# Chronograph.net
KiCad netlist of a schematic drawn in EAGLE
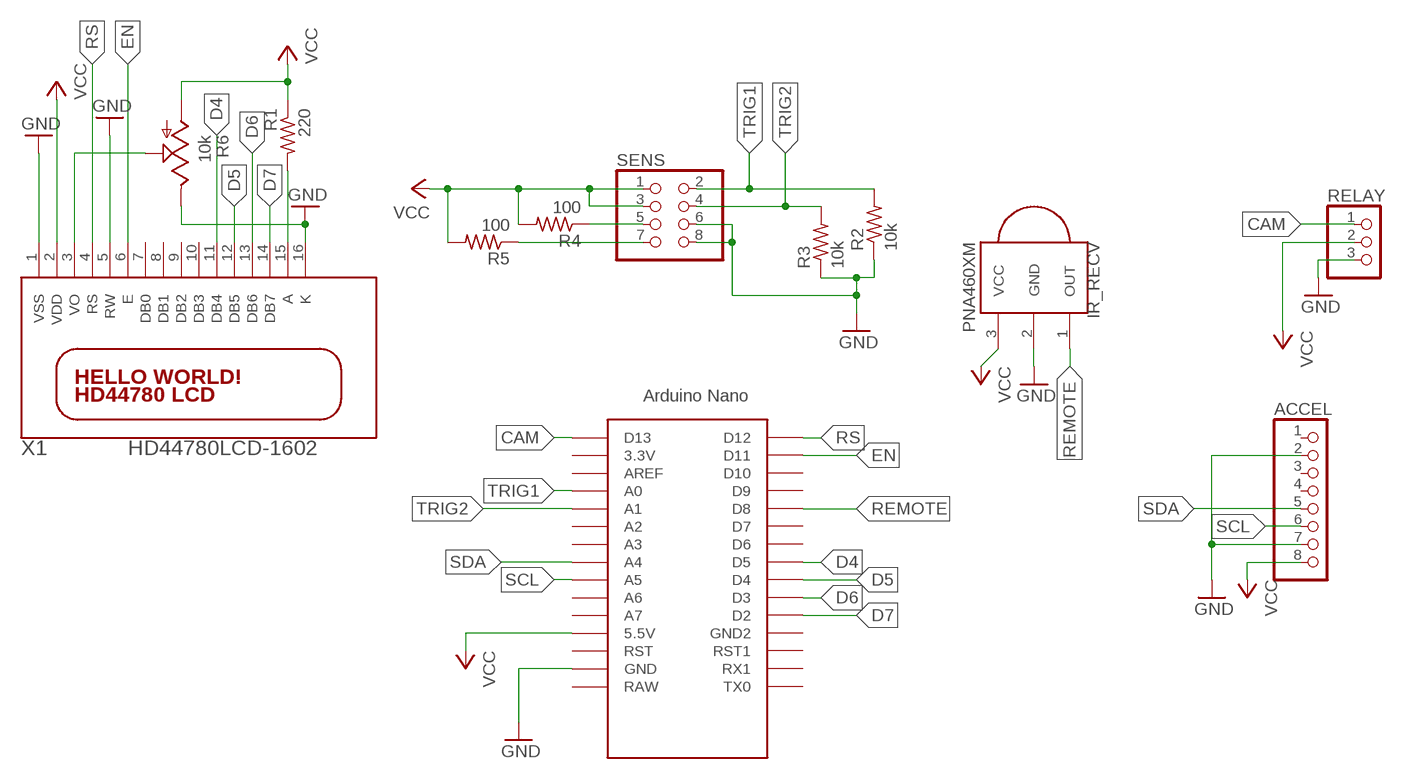
[diagram p0: schematic, sheet 1]

(export (version "E")
  (design (tool "Eeschema 10.0.6"))
  (components
    (comp (ref "ACCEL")
      (value "PINHD-1X8BIG")
      (footprint "eagle-import:1X08-BIG")
      (libsource (lib "eagle-import") (part "PINHD-1X8BIG"))
    )
    (comp (ref "IR_RECV")
      (value "PNA460XM")
      (footprint "eagle-import:PNA460XM")
      (libsource (lib "eagle-import") (part "PNA460XM"))
    )
    (comp (ref "R1")
      (value "220")
      (footprint "eagle-import:0204_7")
      (libsource (lib "eagle-import") (part "R-US_0204/7"))
    )
    (comp (ref "R2")
      (value "10k")
      (footprint "eagle-import:0204_7")
      (libsource (lib "eagle-import") (part "R-US_0204/7"))
    )
    (comp (ref "R3")
      (value "10k")
      (footprint "eagle-import:0204_7")
      (libsource (lib "eagle-import") (part "R-US_0204/7"))
    )
    (comp (ref "R4")
      (value "100")
      (footprint "eagle-import:0204_7")
      (libsource (lib "eagle-import") (part "R-US_0204/7"))
    )
    (comp (ref "R5")
      (value "100")
      (footprint "eagle-import:0204_7")
      (libsource (lib "eagle-import") (part "R-US_0204/7"))
    )
    (comp (ref "R6")
      (value "10k")
      (footprint "eagle-import:B64Y")
      (libsource (lib "eagle-import") (part "TRIM_US-B64Y"))
    )
    (comp (ref "RELAY")
      (value "PINHD-1X3")
      (footprint "eagle-import:1X03")
      (libsource (lib "eagle-import") (part "PINHD-1X3"))
    )
    (comp (ref "SENS")
      (value "PINHD-2X4")
      (footprint "eagle-import:2X04")
      (libsource (lib "eagle-import") (part "PINHD-2X4"))
    )
    (comp (ref "U$1")
      (value "NANO")
      (footprint "eagle-import:NANO")
      (libsource (lib "eagle-import") (part "NANO"))
    )
    (comp (ref "X1")
      (value "HD44780LCD-1602")
      (footprint "eagle-import:LCD1602")
      (libsource (lib "eagle-import") (part "HD44780LCD-1602"))
    )
  )
  (nets
    (net (code "1") (name "CAM") (class "Default")
      (node (ref "RELAY") (pin "1") (pinfunction "1_1") (pintype "passive"))
      (node (ref "U$1") (pin "D13") (pinfunction "D13_D13") (pintype "bidirectional"))
    )
    (net (code "2") (name "D4") (class "Default")
      (node (ref "U$1") (pin "D5") (pinfunction "D5_D5") (pintype "bidirectional"))
      (node (ref "X1") (pin "11") (pinfunction "DB4_11") (pintype "bidirectional"))
    )
    (net (code "3") (name "D5") (class "Default")
      (node (ref "U$1") (pin "D4") (pinfunction "D4_D4") (pintype "bidirectional"))
      (node (ref "X1") (pin "12") (pinfunction "DB5_12") (pintype "bidirectional"))
    )
    (net (code "4") (name "D6") (class "Default")
      (node (ref "U$1") (pin "D3") (pinfunction "D3_D3") (pintype "bidirectional"))
      (node (ref "X1") (pin "13") (pinfunction "DB6_13") (pintype "bidirectional"))
    )
    (net (code "5") (name "D7") (class "Default")
      (node (ref "U$1") (pin "D2") (pinfunction "D2_D2") (pintype "bidirectional"))
      (node (ref "X1") (pin "14") (pinfunction "DB7_14") (pintype "bidirectional"))
    )
    (net (code "6") (name "EN") (class "Default")
      (node (ref "U$1") (pin "D11") (pinfunction "D11_D11") (pintype "bidirectional"))
      (node (ref "X1") (pin "6") (pinfunction "E_6") (pintype "input"))
    )
    (net (code "7") (name "GND") (class "Default")
      (node (ref "ACCEL") (pin "2") (pinfunction "2_2") (pintype "passive"))
      (node (ref "ACCEL") (pin "7") (pinfunction "7_7") (pintype "passive"))
      (node (ref "IR_RECV") (pin "2") (pinfunction "GND_2") (pintype "power_in"))
      (node (ref "R2") (pin "1") (pinfunction "1_1") (pintype "passive"))
      (node (ref "R3") (pin "1") (pinfunction "1_1") (pintype "passive"))
      (node (ref "R6") (pin "E") (pinfunction "E_E") (pintype "passive"))
      (node (ref "RELAY") (pin "3") (pinfunction "3_3") (pintype "passive"))
      (node (ref "SENS") (pin "6") (pinfunction "6_6") (pintype "passive"))
      (node (ref "SENS") (pin "8") (pinfunction "8_8") (pintype "passive"))
      (node (ref "U$1") (pin "GND") (pinfunction "GND_GND") (pintype "bidirectional"))
      (node (ref "X1") (pin "1") (pinfunction "VSS_1") (pintype "power_in"))
      (node (ref "X1") (pin "16") (pinfunction "K_16") (pintype "input"))
      (node (ref "X1") (pin "5") (pinfunction "RW_5") (pintype "input"))
    )
    (net (code "8") (name "Net-(R4-Pad1)") (class "Default")
      (node (ref "R4") (pin "1") (pinfunction "1_1") (pintype "passive"))
      (node (ref "SENS") (pin "5") (pinfunction "5_5") (pintype "passive"))
    )
    (net (code "9") (name "Net-(R5-Pad1)") (class "Default")
      (node (ref "R5") (pin "1") (pinfunction "1_1") (pintype "passive"))
      (node (ref "SENS") (pin "7") (pinfunction "7_7") (pintype "passive"))
    )
    (net (code "10") (name "Net-(X1-A)") (class "Default")
      (node (ref "R1") (pin "2") (pinfunction "2_2") (pintype "passive"))
      (node (ref "X1") (pin "15") (pinfunction "A_15") (pintype "input"))
    )
    (net (code "11") (name "Net-(X1-VO)") (class "Default")
      (node (ref "R6") (pin "S") (pinfunction "S_S") (pintype "passive"))
      (node (ref "X1") (pin "3") (pinfunction "VO_3") (pintype "input"))
    )
    (net (code "12") (name "REMOTE") (class "Default")
      (node (ref "IR_RECV") (pin "1") (pinfunction "OUT_1") (pintype "output"))
      (node (ref "U$1") (pin "D8") (pinfunction "D8_D8") (pintype "bidirectional"))
    )
    (net (code "13") (name "RS") (class "Default")
      (node (ref "U$1") (pin "D12") (pinfunction "D12_D12") (pintype "bidirectional"))
      (node (ref "X1") (pin "4") (pinfunction "RS_4") (pintype "input"))
    )
    (net (code "14") (name "SCL") (class "Default")
      (node (ref "ACCEL") (pin "6") (pinfunction "6_6") (pintype "passive"))
      (node (ref "U$1") (pin "A5") (pinfunction "A5_A5") (pintype "bidirectional"))
    )
    (net (code "15") (name "SDA") (class "Default")
      (node (ref "ACCEL") (pin "5") (pinfunction "5_5") (pintype "passive"))
      (node (ref "U$1") (pin "A4") (pinfunction "A4_A4") (pintype "bidirectional"))
    )
    (net (code "16") (name "TRIG1") (class "Default")
      (node (ref "R2") (pin "2") (pinfunction "2_2") (pintype "passive"))
      (node (ref "SENS") (pin "2") (pinfunction "2_2") (pintype "passive"))
      (node (ref "U$1") (pin "A0") (pinfunction "A0_A0") (pintype "bidirectional"))
    )
    (net (code "17") (name "TRIG2") (class "Default")
      (node (ref "R3") (pin "2") (pinfunction "2_2") (pintype "passive"))
      (node (ref "SENS") (pin "4") (pinfunction "4_4") (pintype "passive"))
      (node (ref "U$1") (pin "A1") (pinfunction "A1_A1") (pintype "bidirectional"))
    )
    (net (code "18") (name "VCC") (class "Default")
      (node (ref "ACCEL") (pin "8") (pinfunction "8_8") (pintype "passive"))
      (node (ref "IR_RECV") (pin "3") (pinfunction "VCC_3") (pintype "power_in"))
      (node (ref "R1") (pin "1") (pinfunction "1_1") (pintype "passive"))
      (node (ref "R4") (pin "2") (pinfunction "2_2") (pintype "passive"))
      (node (ref "R5") (pin "2") (pinfunction "2_2") (pintype "passive"))
      (node (ref "R6") (pin "A") (pinfunction "A_A") (pintype "passive"))
      (node (ref "RELAY") (pin "2") (pinfunction "2_2") (pintype "passive"))
      (node (ref "SENS") (pin "1") (pinfunction "1_1") (pintype "passive"))
      (node (ref "SENS") (pin "3") (pinfunction "3_3") (pintype "passive"))
      (node (ref "U$1") (pin "5V") (pinfunction "5.5V_5V") (pintype "bidirectional"))
      (node (ref "X1") (pin "2") (pinfunction "VDD_2") (pintype "power_in"))
    )
    (net (code "19") (name "unconnected-(ACCEL-Pad1)") (class "Default")
      (node (ref "ACCEL") (pin "1") (pinfunction "1_1") (pintype "passive"))
    )
    (net (code "20") (name "unconnected-(ACCEL-Pad3)") (class "Default")
      (node (ref "ACCEL") (pin "3") (pinfunction "3_3") (pintype "passive"))
    )
    (net (code "21") (name "unconnected-(ACCEL-Pad4)") (class "Default")
      (node (ref "ACCEL") (pin "4") (pinfunction "4_4") (pintype "passive"))
    )
    (net (code "22") (name "unconnected-(U$1-GND2-PadGND1)") (class "Default")
      (node (ref "U$1") (pin "GND1") (pinfunction "GND2_GND1") (pintype "bidirectional"))
    )
    (net (code "23") (name "unconnected-(U$1-Pad3.3V)") (class "Default")
      (node (ref "U$1") (pin "3.3V") (pinfunction "3.3V_3.3V") (pintype "bidirectional"))
    )
    (net (code "24") (name "unconnected-(U$1-PadA2)") (class "Default")
      (node (ref "U$1") (pin "A2") (pinfunction "A2_A2") (pintype "bidirectional"))
    )
    (net (code "25") (name "unconnected-(U$1-PadA3)") (class "Default")
      (node (ref "U$1") (pin "A3") (pinfunction "A3_A3") (pintype "bidirectional"))
    )
    (net (code "26") (name "unconnected-(U$1-PadA6)") (class "Default")
      (node (ref "U$1") (pin "A6") (pinfunction "A6_A6") (pintype "bidirectional"))
    )
    (net (code "27") (name "unconnected-(U$1-PadA7)") (class "Default")
      (node (ref "U$1") (pin "A7") (pinfunction "A7_A7") (pintype "bidirectional"))
    )
    (net (code "28") (name "unconnected-(U$1-PadAREF)") (class "Default")
      (node (ref "U$1") (pin "AREF") (pinfunction "AREF_AREF") (pintype "bidirectional"))
    )
    (net (code "29") (name "unconnected-(U$1-PadD6)") (class "Default")
      (node (ref "U$1") (pin "D6") (pinfunction "D6_D6") (pintype "bidirectional"))
    )
    (net (code "30") (name "unconnected-(U$1-PadD7)") (class "Default")
      (node (ref "U$1") (pin "D7") (pinfunction "D7_D7") (pintype "bidirectional"))
    )
    (net (code "31") (name "unconnected-(U$1-PadD9)") (class "Default")
      (node (ref "U$1") (pin "D9") (pinfunction "D9_D9") (pintype "bidirectional"))
    )
    (net (code "32") (name "unconnected-(U$1-PadD10)") (class "Default")
      (node (ref "U$1") (pin "D10") (pinfunction "D10_D10") (pintype "bidirectional"))
    )
    (net (code "33") (name "unconnected-(U$1-PadICSP1)") (class "Default")
      (node (ref "U$1") (pin "ICSP1") (pinfunction "ICSP1_ICSP1") (pintype "bidirectional"))
    )
    (net (code "34") (name "unconnected-(U$1-PadICSP2)") (class "Default")
      (node (ref "U$1") (pin "ICSP2") (pinfunction "ICSP2_ICSP2") (pintype "bidirectional"))
    )
    (net (code "35") (name "unconnected-(U$1-PadICSP3)") (class "Default")
      (node (ref "U$1") (pin "ICSP3") (pinfunction "ICSP3_ICSP3") (pintype "bidirectional"))
    )
    (net (code "36") (name "unconnected-(U$1-PadICSP4)") (class "Default")
      (node (ref "U$1") (pin "ICSP4") (pinfunction "ICSP4_ICSP4") (pintype "bidirectional"))
    )
    (net (code "37") (name "unconnected-(U$1-PadICSP5)") (class "Default")
      (node (ref "U$1") (pin "ICSP5") (pinfunction "ICSP5_ICSP5") (pintype "bidirectional"))
    )
    (net (code "38") (name "unconnected-(U$1-PadICSP6)") (class "Default")
      (node (ref "U$1") (pin "ICSP6") (pinfunction "ICSP6_ICSP6") (pintype "bidirectional"))
    )
    (net (code "39") (name "unconnected-(U$1-PadRAW)") (class "Default")
      (node (ref "U$1") (pin "RAW") (pinfunction "RAW_RAW") (pintype "bidirectional"))
    )
    (net (code "40") (name "unconnected-(U$1-PadRST)") (class "Default")
      (node (ref "U$1") (pin "RST") (pinfunction "RST_RST") (pintype "bidirectional"))
    )
    (net (code "41") (name "unconnected-(U$1-PadRST1)") (class "Default")
      (node (ref "U$1") (pin "RST1") (pinfunction "RST1_RST1") (pintype "bidirectional"))
    )
    (net (code "42") (name "unconnected-(U$1-PadRX1)") (class "Default")
      (node (ref "U$1") (pin "RX1") (pinfunction "RX1_RX1") (pintype "bidirectional"))
    )
    (net (code "43") (name "unconnected-(U$1-PadTX0)") (class "Default")
      (node (ref "U$1") (pin "TX0") (pinfunction "TX0_TX0") (pintype "bidirectional"))
    )
    (net (code "44") (name "unconnected-(X1-DB0-Pad7)") (class "Default")
      (node (ref "X1") (pin "7") (pinfunction "DB0_7") (pintype "bidirectional"))
    )
    (net (code "45") (name "unconnected-(X1-DB1-Pad8)") (class "Default")
      (node (ref "X1") (pin "8") (pinfunction "DB1_8") (pintype "bidirectional"))
    )
    (net (code "46") (name "unconnected-(X1-DB2-Pad9)") (class "Default")
      (node (ref "X1") (pin "9") (pinfunction "DB2_9") (pintype "bidirectional"))
    )
    (net (code "47") (name "unconnected-(X1-DB3-Pad10)") (class "Default")
      (node (ref "X1") (pin "10") (pinfunction "DB3_10") (pintype "bidirectional"))
    )
  )
)
